# EEPROM.net
KiCad netlist of a schematic drawn in Altium Designer
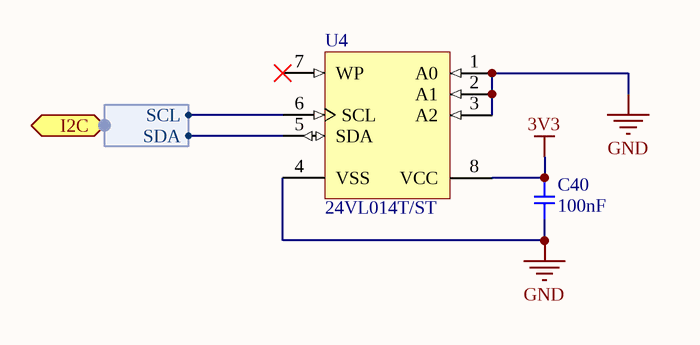
[diagram p0: EEPROM.SchDoc]

(export (version "E")
  (design (tool "Eeschema 10.0.6"))
  (components
    (comp (ref "C40")
      (value "100nF")
      (footprint "SMD-0603C")
      (description "CAP CER 0.1UF 16V X7R 0603")
      (fields
        (field (name "DIGI-KEY PART NUMBER") "490-5796-1-ND")
        (field (name "PART NUMBER") "GCJ188R71C104KA01D")
      )
      (libsource (lib "capacitor_murata_0603") (part "GCJ188R71C104KA01D"))
    )
    (comp (ref "U4")
      (value "24VL014T/ST")
      (footprint "TSSOP-ST8_N")
      (description "1K I2C Serial EEPROM, 8-Pin TSSOP, Industrial Temperature, Tape and Reel")
      (fields (field (name "MANUFACTURER") "Microchip"))
      (libsource (lib "Microchip I2C Serial EEPROM") (part "24VL014T/ST"))
    )
  )
  (nets
    (net (code "2") (name "/SCL") (class "Default")
      (node (ref "U4") (pin "6") (pinfunction "SCL_6") (pintype "input"))
    )
    (net (code "3") (name "/SDA") (class "Default")
      (node (ref "U4") (pin "5") (pinfunction "SDA_5") (pintype "bidirectional"))
    )
    (net (code "5") (name "3V3") (class "Default")
      (node (ref "C40") (pin "1") (pinfunction "1_1") (pintype "passive"))
      (node (ref "U4") (pin "8") (pinfunction "VCC_8") (pintype "power_in"))
    )
    (net (code "6") (name "GND") (class "Default")
      (node (ref "C40") (pin "2") (pinfunction "2_2") (pintype "passive"))
      (node (ref "U4") (pin "1") (pinfunction "A0_1") (pintype "input"))
      (node (ref "U4") (pin "2") (pinfunction "A1_2") (pintype "input"))
      (node (ref "U4") (pin "3") (pinfunction "A2_3") (pintype "input"))
      (node (ref "U4") (pin "4") (pinfunction "VSS_4") (pintype "power_in"))
    )
    (net (code "7") (name "unconnected-(U4-WP-Pad7)") (class "Default")
      (node (ref "U4") (pin "7") (pinfunction "WP_7") (pintype "input+no_connect"))
    )
  )
)
